# P17_Hi3531AV100.net
KiCad netlist of a schematic drawn in Altium Designer
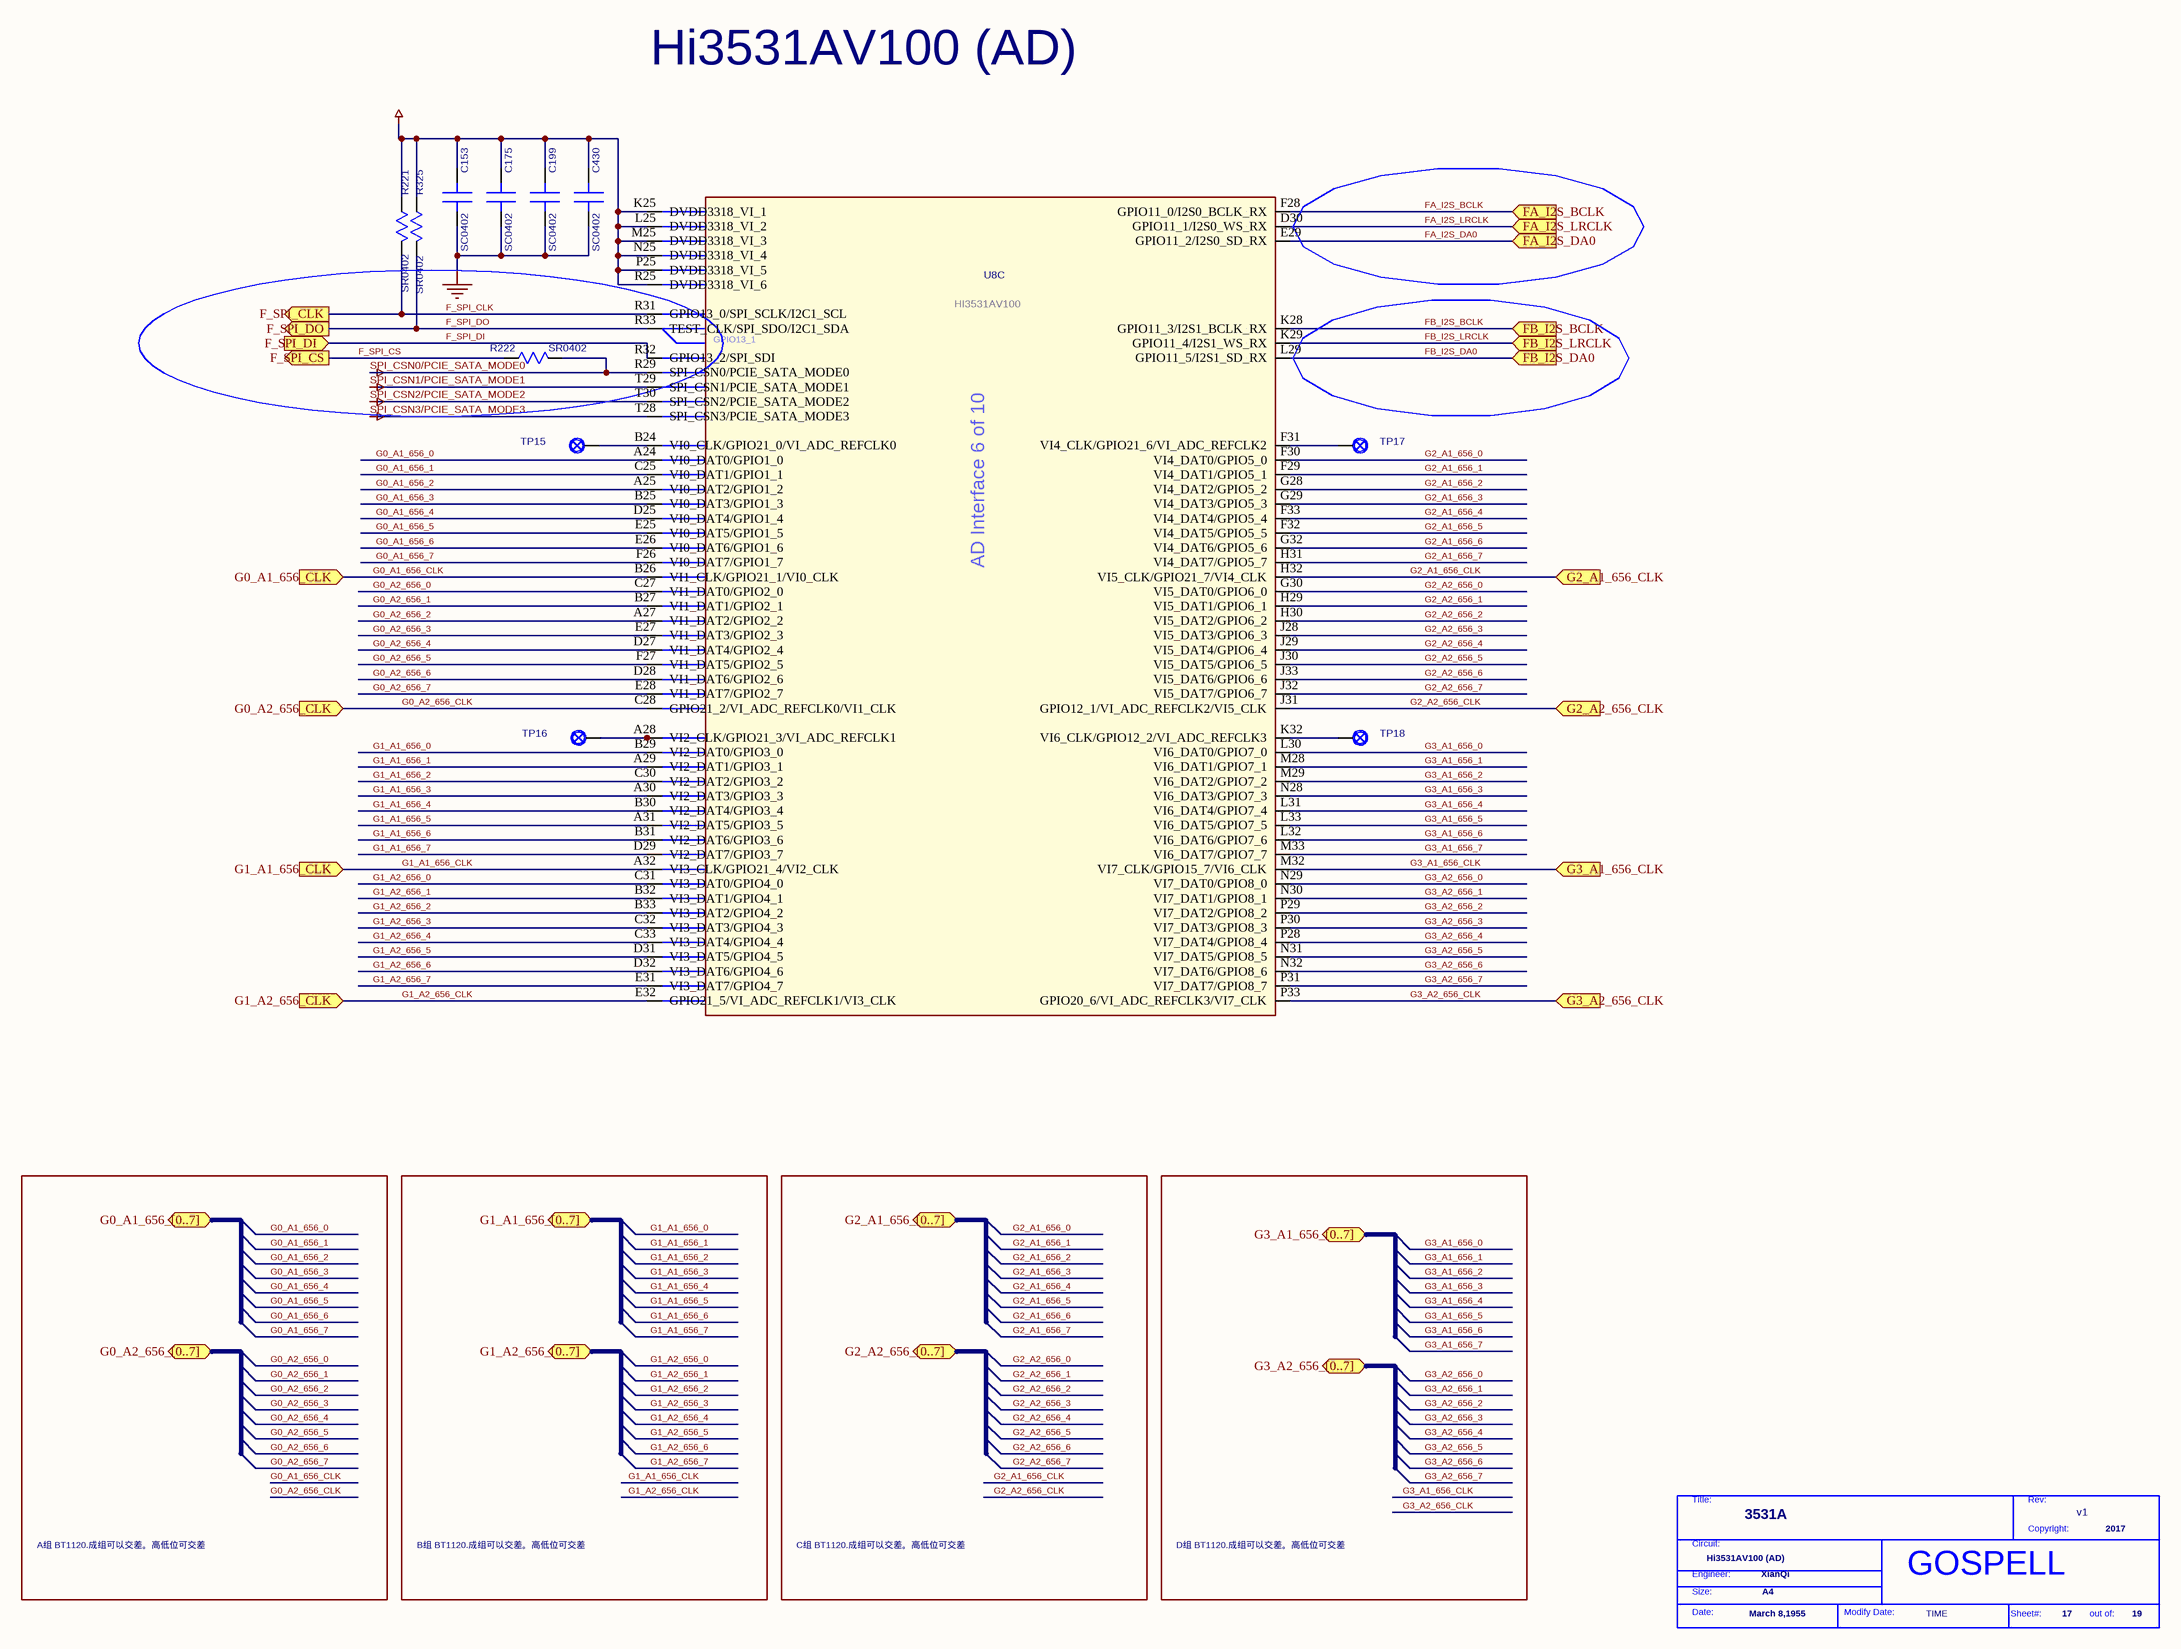
[diagram p0: P17 Hi3531AV100 (AD).SchDoc]

(export (version "E")
  (design (tool "Eeschema 10.0.6"))
  (components
    (comp (ref "C153") (value "SC0402") (libsource (lib "*") (part "C_0_Dup2")))
    (comp (ref "C175") (value "SC0402") (libsource (lib "*") (part "C_0_Dup2")))
    (comp (ref "C199") (value "SC0402") (libsource (lib "*") (part "C_0_Dup2")))
    (comp (ref "C430") (value "SC0402") (libsource (lib "*") (part "C_0_Dup2")))
    (comp (ref "R221") (value "SR0402") (libsource (lib "*") (part "R_1")))
    (comp (ref "R222") (value "SR0402") (libsource (lib "*") (part "R_1")))
    (comp (ref "R325") (value "SR0402") (libsource (lib "*") (part "R_1")))
    (comp (ref "TP15") (value "TP24-SMD") (libsource (lib "*") (part "TESTPOINT_0")))
    (comp (ref "TP16") (value "TP24-SMD") (libsource (lib "*") (part "TESTPOINT_0")))
    (comp (ref "TP17") (value "TP24-SMD") (libsource (lib "*") (part "TESTPOINT_0")))
    (comp (ref "TP18") (value "TP24-SMD") (libsource (lib "*") (part "TESTPOINT_0")))
    (comp (ref "U8")
      (value "BGA805-32-3333")
      (fields (field (name "DEVICE") "HI3531AV100"))
      (libsource (lib "*") (part "HI3531AV100_M2_17"))
    )
  )
  (nets
    (net (code "1") (name "/FA_I2S_BCLK") (class "Default")
      (node (ref "U8") (pin "F28") (pinfunction "GPIO11_0/I2S0_BCLK_RX_F28") (pintype "passive"))
    )
    (net (code "2") (name "/FA_I2S_DA0") (class "Default")
      (node (ref "U8") (pin "E29") (pinfunction "GPIO11_2/I2S0_SD_RX_E29") (pintype "passive"))
    )
    (net (code "3") (name "/FA_I2S_LRCLK") (class "Default")
      (node (ref "U8") (pin "D30") (pinfunction "GPIO11_1/I2S0_WS_RX_D30") (pintype "passive"))
    )
    (net (code "4") (name "/FB_I2S_BCLK") (class "Default")
      (node (ref "U8") (pin "K28") (pinfunction "GPIO11_3/I2S1_BCLK_RX_K28") (pintype "passive"))
    )
    (net (code "5") (name "/FB_I2S_DA0") (class "Default")
      (node (ref "U8") (pin "L29") (pinfunction "GPIO11_5/I2S1_SD_RX_L29") (pintype "passive"))
    )
    (net (code "6") (name "/FB_I2S_LRCLK") (class "Default")
      (node (ref "U8") (pin "K29") (pinfunction "GPIO11_4/I2S1_WS_RX_K29") (pintype "passive"))
    )
    (net (code "7") (name "/F_SPI_CLK") (class "Default")
      (node (ref "R221") (pin "2") (pinfunction "B_2") (pintype "passive"))
      (node (ref "U8") (pin "R31") (pinfunction "GPIO13_0/SPI_SCLK/I2C1_SCL_R31") (pintype "passive"))
    )
    (net (code "8") (name "/F_SPI_CS") (class "Default")
      (node (ref "R222") (pin "1") (pinfunction "A_1") (pintype "passive"))
    )
    (net (code "9") (name "/F_SPI_DI") (class "Default")
      (node (ref "U8") (pin "R32") (pinfunction "GPIO13_2/SPI_SDI_R32") (pintype "passive"))
    )
    (net (code "10") (name "/F_SPI_DO") (class "Default")
      (node (ref "R325") (pin "2") (pinfunction "B_2") (pintype "passive"))
      (node (ref "U8") (pin "R33") (pinfunction "TEST_CLK/SPI_SDO/I2C1_SDA_R33") (pintype "passive"))
    )
    (net (code "11") (name "/G0_A1_656_0") (class "Default")
      (node (ref "U8") (pin "A24") (pinfunction "VI0_DAT0/GPIO1_0_A24") (pintype "passive"))
    )
    (net (code "12") (name "/G0_A1_656_1") (class "Default")
      (node (ref "U8") (pin "C25") (pinfunction "VI0_DAT1/GPIO1_1_C25") (pintype "passive"))
    )
    (net (code "13") (name "/G0_A1_656_2") (class "Default")
      (node (ref "U8") (pin "A25") (pinfunction "VI0_DAT2/GPIO1_2_A25") (pintype "passive"))
    )
    (net (code "14") (name "/G0_A1_656_3") (class "Default")
      (node (ref "U8") (pin "B25") (pinfunction "VI0_DAT3/GPIO1_3_B25") (pintype "passive"))
    )
    (net (code "15") (name "/G0_A1_656_4") (class "Default")
      (node (ref "U8") (pin "D25") (pinfunction "VI0_DAT4/GPIO1_4_D25") (pintype "passive"))
    )
    (net (code "16") (name "/G0_A1_656_5") (class "Default")
      (node (ref "U8") (pin "E25") (pinfunction "VI0_DAT5/GPIO1_5_E25") (pintype "passive"))
    )
    (net (code "17") (name "/G0_A1_656_6") (class "Default")
      (node (ref "U8") (pin "E26") (pinfunction "VI0_DAT6/GPIO1_6_E26") (pintype "passive"))
    )
    (net (code "18") (name "/G0_A1_656_7") (class "Default")
      (node (ref "U8") (pin "F26") (pinfunction "VI0_DAT7/GPIO1_7_F26") (pintype "passive"))
    )
    (net (code "19") (name "/G0_A1_656_CLK") (class "Default")
      (node (ref "U8") (pin "B26") (pinfunction "VI1_CLK/GPIO21_1/VI0_CLK_B26") (pintype "passive"))
    )
    (net (code "21") (name "/G0_A2_656_0") (class "Default")
      (node (ref "U8") (pin "C27") (pinfunction "VI1_DAT0/GPIO2_0_C27") (pintype "passive"))
    )
    (net (code "22") (name "/G0_A2_656_1") (class "Default")
      (node (ref "U8") (pin "B27") (pinfunction "VI1_DAT1/GPIO2_1_B27") (pintype "passive"))
    )
    (net (code "23") (name "/G0_A2_656_2") (class "Default")
      (node (ref "U8") (pin "A27") (pinfunction "VI1_DAT2/GPIO2_2_A27") (pintype "passive"))
    )
    (net (code "24") (name "/G0_A2_656_3") (class "Default")
      (node (ref "U8") (pin "E27") (pinfunction "VI1_DAT3/GPIO2_3_E27") (pintype "passive"))
    )
    (net (code "25") (name "/G0_A2_656_4") (class "Default")
      (node (ref "U8") (pin "D27") (pinfunction "VI1_DAT4/GPIO2_4_D27") (pintype "passive"))
    )
    (net (code "26") (name "/G0_A2_656_5") (class "Default")
      (node (ref "U8") (pin "F27") (pinfunction "VI1_DAT5/GPIO2_5_F27") (pintype "passive"))
    )
    (net (code "27") (name "/G0_A2_656_6") (class "Default")
      (node (ref "U8") (pin "D28") (pinfunction "VI1_DAT6/GPIO2_6_D28") (pintype "passive"))
    )
    (net (code "28") (name "/G0_A2_656_7") (class "Default")
      (node (ref "U8") (pin "E28") (pinfunction "VI1_DAT7/GPIO2_7_E28") (pintype "passive"))
    )
    (net (code "29") (name "/G0_A2_656_CLK") (class "Default")
      (node (ref "U8") (pin "C28") (pinfunction "GPIO21_2/VI_ADC_REFCLK0/VI1_CLK_C28") (pintype "passive"))
    )
    (net (code "31") (name "/G1_A1_656_0") (class "Default")
      (node (ref "U8") (pin "B29") (pinfunction "VI2_DAT0/GPIO3_0_B29") (pintype "passive"))
    )
    (net (code "32") (name "/G1_A1_656_1") (class "Default")
      (node (ref "U8") (pin "A29") (pinfunction "VI2_DAT1/GPIO3_1_A29") (pintype "passive"))
    )
    (net (code "33") (name "/G1_A1_656_2") (class "Default")
      (node (ref "U8") (pin "C30") (pinfunction "VI2_DAT2/GPIO3_2_C30") (pintype "passive"))
    )
    (net (code "34") (name "/G1_A1_656_3") (class "Default")
      (node (ref "U8") (pin "A30") (pinfunction "VI2_DAT3/GPIO3_3_A30") (pintype "passive"))
    )
    (net (code "35") (name "/G1_A1_656_4") (class "Default")
      (node (ref "U8") (pin "B30") (pinfunction "VI2_DAT4/GPIO3_4_B30") (pintype "passive"))
    )
    (net (code "36") (name "/G1_A1_656_5") (class "Default")
      (node (ref "U8") (pin "A31") (pinfunction "VI2_DAT5/GPIO3_5_A31") (pintype "passive"))
    )
    (net (code "37") (name "/G1_A1_656_6") (class "Default")
      (node (ref "U8") (pin "B31") (pinfunction "VI2_DAT6/GPIO3_6_B31") (pintype "passive"))
    )
    (net (code "38") (name "/G1_A1_656_7") (class "Default")
      (node (ref "U8") (pin "D29") (pinfunction "VI2_DAT7/GPIO3_7_D29") (pintype "passive"))
    )
    (net (code "39") (name "/G1_A1_656_CLK") (class "Default")
      (node (ref "U8") (pin "A32") (pinfunction "VI3_CLK/GPIO21_4/VI2_CLK_A32") (pintype "passive"))
    )
    (net (code "41") (name "/G1_A2_656_0") (class "Default")
      (node (ref "U8") (pin "C31") (pinfunction "VI3_DAT0/GPIO4_0_C31") (pintype "passive"))
    )
    (net (code "42") (name "/G1_A2_656_1") (class "Default")
      (node (ref "U8") (pin "B32") (pinfunction "VI3_DAT1/GPIO4_1_B32") (pintype "passive"))
    )
    (net (code "43") (name "/G1_A2_656_2") (class "Default")
      (node (ref "U8") (pin "B33") (pinfunction "VI3_DAT2/GPIO4_2_B33") (pintype "passive"))
    )
    (net (code "44") (name "/G1_A2_656_3") (class "Default")
      (node (ref "U8") (pin "C32") (pinfunction "VI3_DAT3/GPIO4_3_C32") (pintype "passive"))
    )
    (net (code "45") (name "/G1_A2_656_4") (class "Default")
      (node (ref "U8") (pin "C33") (pinfunction "VI3_DAT4/GPIO4_4_C33") (pintype "passive"))
    )
    (net (code "46") (name "/G1_A2_656_5") (class "Default")
      (node (ref "U8") (pin "D31") (pinfunction "VI3_DAT5/GPIO4_5_D31") (pintype "passive"))
    )
    (net (code "47") (name "/G1_A2_656_6") (class "Default")
      (node (ref "U8") (pin "D32") (pinfunction "VI3_DAT6/GPIO4_6_D32") (pintype "passive"))
    )
    (net (code "48") (name "/G1_A2_656_7") (class "Default")
      (node (ref "U8") (pin "E31") (pinfunction "VI3_DAT7/GPIO4_7_E31") (pintype "passive"))
    )
    (net (code "49") (name "/G1_A2_656_CLK") (class "Default")
      (node (ref "U8") (pin "E32") (pinfunction "GPIO21_5/VI_ADC_REFCLK1/VI3_CLK_E32") (pintype "passive"))
    )
    (net (code "51") (name "/G2_A1_656_0") (class "Default")
      (node (ref "U8") (pin "F30") (pinfunction "VI4_DAT0/GPIO5_0_F30") (pintype "passive"))
    )
    (net (code "52") (name "/G2_A1_656_1") (class "Default")
      (node (ref "U8") (pin "F29") (pinfunction "VI4_DAT1/GPIO5_1_F29") (pintype "passive"))
    )
    (net (code "53") (name "/G2_A1_656_2") (class "Default")
      (node (ref "U8") (pin "G28") (pinfunction "VI4_DAT2/GPIO5_2_G28") (pintype "passive"))
    )
    (net (code "54") (name "/G2_A1_656_3") (class "Default")
      (node (ref "U8") (pin "G29") (pinfunction "VI4_DAT3/GPIO5_3_G29") (pintype "passive"))
    )
    (net (code "55") (name "/G2_A1_656_4") (class "Default")
      (node (ref "U8") (pin "F33") (pinfunction "VI4_DAT4/GPIO5_4_F33") (pintype "passive"))
    )
    (net (code "56") (name "/G2_A1_656_5") (class "Default")
      (node (ref "U8") (pin "F32") (pinfunction "VI4_DAT5/GPIO5_5_F32") (pintype "passive"))
    )
    (net (code "57") (name "/G2_A1_656_6") (class "Default")
      (node (ref "U8") (pin "G32") (pinfunction "VI4_DAT6/GPIO5_6_G32") (pintype "passive"))
    )
    (net (code "58") (name "/G2_A1_656_7") (class "Default")
      (node (ref "U8") (pin "H31") (pinfunction "VI4_DAT7/GPIO5_7_H31") (pintype "passive"))
    )
    (net (code "59") (name "/G2_A1_656_CLK") (class "Default")
      (node (ref "U8") (pin "H32") (pinfunction "VI5_CLK/GPIO21_7/VI4_CLK_H32") (pintype "passive"))
    )
    (net (code "61") (name "/G2_A2_656_0") (class "Default")
      (node (ref "U8") (pin "G30") (pinfunction "VI5_DAT0/GPIO6_0_G30") (pintype "passive"))
    )
    (net (code "62") (name "/G2_A2_656_1") (class "Default")
      (node (ref "U8") (pin "H29") (pinfunction "VI5_DAT1/GPIO6_1_H29") (pintype "passive"))
    )
    (net (code "63") (name "/G2_A2_656_2") (class "Default")
      (node (ref "U8") (pin "H30") (pinfunction "VI5_DAT2/GPIO6_2_H30") (pintype "passive"))
    )
    (net (code "64") (name "/G2_A2_656_3") (class "Default")
      (node (ref "U8") (pin "J28") (pinfunction "VI5_DAT3/GPIO6_3_J28") (pintype "passive"))
    )
    (net (code "65") (name "/G2_A2_656_4") (class "Default")
      (node (ref "U8") (pin "J29") (pinfunction "VI5_DAT4/GPIO6_4_J29") (pintype "passive"))
    )
    (net (code "66") (name "/G2_A2_656_5") (class "Default")
      (node (ref "U8") (pin "J30") (pinfunction "VI5_DAT5/GPIO6_5_J30") (pintype "passive"))
    )
    (net (code "67") (name "/G2_A2_656_6") (class "Default")
      (node (ref "U8") (pin "J33") (pinfunction "VI5_DAT6/GPIO6_6_J33") (pintype "passive"))
    )
    (net (code "68") (name "/G2_A2_656_7") (class "Default")
      (node (ref "U8") (pin "J32") (pinfunction "VI5_DAT7/GPIO6_7_J32") (pintype "passive"))
    )
    (net (code "69") (name "/G2_A2_656_CLK") (class "Default")
      (node (ref "U8") (pin "J31") (pinfunction "GPIO12_1/VI_ADC_REFCLK2/VI5_CLK_J31") (pintype "passive"))
    )
    (net (code "71") (name "/G3_A1_656_0") (class "Default")
      (node (ref "U8") (pin "L30") (pinfunction "VI6_DAT0/GPIO7_0_L30") (pintype "passive"))
    )
    (net (code "72") (name "/G3_A1_656_1") (class "Default")
      (node (ref "U8") (pin "M28") (pinfunction "VI6_DAT1/GPIO7_1_M28") (pintype "passive"))
    )
    (net (code "73") (name "/G3_A1_656_2") (class "Default")
      (node (ref "U8") (pin "M29") (pinfunction "VI6_DAT2/GPIO7_2_M29") (pintype "passive"))
    )
    (net (code "74") (name "/G3_A1_656_3") (class "Default")
      (node (ref "U8") (pin "N28") (pinfunction "VI6_DAT3/GPIO7_3_N28") (pintype "passive"))
    )
    (net (code "75") (name "/G3_A1_656_4") (class "Default")
      (node (ref "U8") (pin "L31") (pinfunction "VI6_DAT4/GPIO7_4_L31") (pintype "passive"))
    )
    (net (code "76") (name "/G3_A1_656_5") (class "Default")
      (node (ref "U8") (pin "L33") (pinfunction "VI6_DAT5/GPIO7_5_L33") (pintype "passive"))
    )
    (net (code "77") (name "/G3_A1_656_6") (class "Default")
      (node (ref "U8") (pin "L32") (pinfunction "VI6_DAT6/GPIO7_6_L32") (pintype "passive"))
    )
    (net (code "78") (name "/G3_A1_656_7") (class "Default")
      (node (ref "U8") (pin "M33") (pinfunction "VI6_DAT7/GPIO7_7_M33") (pintype "passive"))
    )
    (net (code "79") (name "/G3_A1_656_CLK") (class "Default")
      (node (ref "U8") (pin "M32") (pinfunction "VI7_CLK/GPIO15_7/VI6_CLK_M32") (pintype "passive"))
    )
    (net (code "81") (name "/G3_A2_656_0") (class "Default")
      (node (ref "U8") (pin "N29") (pinfunction "VI7_DAT0/GPIO8_0_N29") (pintype "passive"))
    )
    (net (code "82") (name "/G3_A2_656_1") (class "Default")
      (node (ref "U8") (pin "N30") (pinfunction "VI7_DAT1/GPIO8_1_N30") (pintype "passive"))
    )
    (net (code "83") (name "/G3_A2_656_2") (class "Default")
      (node (ref "U8") (pin "P29") (pinfunction "VI7_DAT2/GPIO8_2_P29") (pintype "passive"))
    )
    (net (code "84") (name "/G3_A2_656_3") (class "Default")
      (node (ref "U8") (pin "P30") (pinfunction "VI7_DAT3/GPIO8_3_P30") (pintype "passive"))
    )
    (net (code "85") (name "/G3_A2_656_4") (class "Default")
      (node (ref "U8") (pin "P28") (pinfunction "VI7_DAT4/GPIO8_4_P28") (pintype "passive"))
    )
    (net (code "86") (name "/G3_A2_656_5") (class "Default")
      (node (ref "U8") (pin "N31") (pinfunction "VI7_DAT5/GPIO8_5_N31") (pintype "passive"))
    )
    (net (code "87") (name "/G3_A2_656_6") (class "Default")
      (node (ref "U8") (pin "N32") (pinfunction "VI7_DAT6/GPIO8_6_N32") (pintype "passive"))
    )
    (net (code "88") (name "/G3_A2_656_7") (class "Default")
      (node (ref "U8") (pin "P31") (pinfunction "VI7_DAT7/GPIO8_7_P31") (pintype "passive"))
    )
    (net (code "89") (name "/G3_A2_656_CLK") (class "Default")
      (node (ref "U8") (pin "P33") (pinfunction "GPIO20_6/VI_ADC_REFCLK3/VI7_CLK_P33") (pintype "passive"))
    )
    (net (code "91") (name "3V3") (class "Default")
      (node (ref "C153") (pin "1") (pinfunction "A_1") (pintype "passive"))
      (node (ref "C175") (pin "1") (pinfunction "A_1") (pintype "passive"))
      (node (ref "C199") (pin "1") (pinfunction "A_1") (pintype "passive"))
      (node (ref "C430") (pin "1") (pinfunction "A_1") (pintype "passive"))
      (node (ref "R221") (pin "1") (pinfunction "A_1") (pintype "passive"))
      (node (ref "R325") (pin "1") (pinfunction "A_1") (pintype "passive"))
      (node (ref "U8") (pin "K25") (pinfunction "DVDD3318_VI_1_K25") (pintype "passive"))
      (node (ref "U8") (pin "L25") (pinfunction "DVDD3318_VI_2_L25") (pintype "passive"))
      (node (ref "U8") (pin "M25") (pinfunction "DVDD3318_VI_3_M25") (pintype "passive"))
      (node (ref "U8") (pin "N25") (pinfunction "DVDD3318_VI_4_N25") (pintype "passive"))
      (node (ref "U8") (pin "P25") (pinfunction "DVDD3318_VI_5_P25") (pintype "passive"))
      (node (ref "U8") (pin "R25") (pinfunction "DVDD3318_VI_6_R25") (pintype "passive"))
    )
    (net (code "92") (name "GND") (class "Default")
      (node (ref "C153") (pin "2") (pinfunction "B_2") (pintype "passive"))
      (node (ref "C175") (pin "2") (pinfunction "B_2") (pintype "passive"))
      (node (ref "C199") (pin "2") (pinfunction "B_2") (pintype "passive"))
      (node (ref "C430") (pin "2") (pinfunction "B_2") (pintype "passive"))
    )
    (net (code "93") (name "Net-(U8C-VI0_CLK{slash}GPIO21_0{slash}VI_ADC_REFCLK0)") (class "Default")
      (node (ref "TP15") (pin "1") (pinfunction "1_1") (pintype "passive"))
      (node (ref "U8") (pin "B24") (pinfunction "VI0_CLK/GPIO21_0/VI_ADC_REFCLK0_B24") (pintype "passive"))
    )
    (net (code "94") (name "Net-(U8C-VI2_CLK{slash}GPIO21_3{slash}VI_ADC_REFCLK1)") (class "Default")
      (node (ref "TP16") (pin "1") (pinfunction "1_1") (pintype "passive"))
      (node (ref "U8") (pin "A28") (pinfunction "VI2_CLK/GPIO21_3/VI_ADC_REFCLK1_A28") (pintype "passive"))
    )
    (net (code "95") (name "Net-(U8C-VI4_CLK{slash}GPIO21_6{slash}VI_ADC_REFCLK2)") (class "Default")
      (node (ref "TP17") (pin "1") (pinfunction "1_1") (pintype "passive"))
      (node (ref "U8") (pin "F31") (pinfunction "VI4_CLK/GPIO21_6/VI_ADC_REFCLK2_F31") (pintype "passive"))
    )
    (net (code "96") (name "Net-(U8C-VI6_CLK{slash}GPIO12_2{slash}VI_ADC_REFCLK3)") (class "Default")
      (node (ref "TP18") (pin "1") (pinfunction "1_1") (pintype "passive"))
      (node (ref "U8") (pin "K32") (pinfunction "VI6_CLK/GPIO12_2/VI_ADC_REFCLK3_K32") (pintype "passive"))
    )
    (net (code "97") (name "SPI_CSN0{slash}PCIE_SATA_MODE0") (class "Default")
      (node (ref "R222") (pin "2") (pinfunction "B_2") (pintype "passive"))
      (node (ref "U8") (pin "R29") (pinfunction "SPI_CSN0/PCIE_SATA_MODE0_R29") (pintype "passive"))
    )
    (net (code "98") (name "SPI_CSN1{slash}PCIE_SATA_MODE1") (class "Default")
      (node (ref "U8") (pin "T29") (pinfunction "SPI_CSN1/PCIE_SATA_MODE1_T29") (pintype "passive"))
    )
    (net (code "99") (name "SPI_CSN2{slash}PCIE_SATA_MODE2") (class "Default")
      (node (ref "U8") (pin "T30") (pinfunction "SPI_CSN2/PCIE_SATA_MODE2_T30") (pintype "passive"))
    )
    (net (code "100") (name "SPI_CSN3{slash}PCIE_SATA_MODE3") (class "Default")
      (node (ref "U8") (pin "T28") (pinfunction "SPI_CSN3/PCIE_SATA_MODE3_T28") (pintype "passive"))
    )
  )
)
